# Regulator.net
KiCad netlist of a schematic drawn in Altium Designer
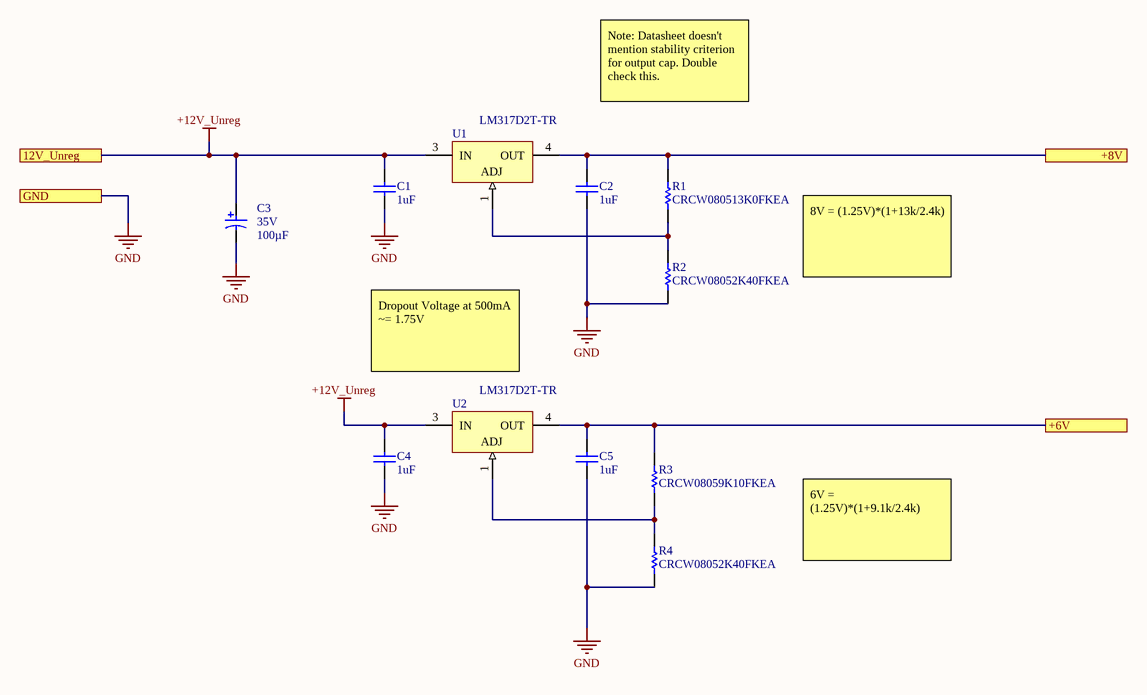
[diagram p0: Regulator.SchDoc]

(export (version "E")
  (design (tool "Eeschema 10.0.6"))
  (components
    (comp (ref "C1")
      (value "1uF")
      (footprint "CAPC2013X100X50NL20T25")
      (fields (field (name "PART NUMBER") "C0805X105K3RACTU") (field (name "MANUFACTURER") "Kemet"))
      (libsource (lib "Altium Content Vault") (part "CAP"))
    )
    (comp (ref "C2")
      (value "1uF")
      (footprint "CAPC2013X100X50NL20T25")
      (fields (field (name "PART NUMBER") "C0805X105K3RACTU") (field (name "MANUFACTURER") "Kemet"))
      (libsource (lib "Altium Content Vault") (part "CAP"))
    )
    (comp (ref "C3")
      (value "EEEFC1V101P")
      (footprint "PNSC-FC-V-G_V")
      (fields
        (field (name "CAPACITANCE") "100µF")
        (field (name "MANUFACTURER") "Panasonic")
        (field (name "VOLTAGE RATING") "35V")
      )
      (libsource (lib "Altium Content Vault") (part "CAP-P-2"))
    )
    (comp (ref "C4")
      (value "1uF")
      (footprint "CAPC2013X100X50NL20T25")
      (fields (field (name "PART NUMBER") "C0805X105K3RACTU") (field (name "MANUFACTURER") "Kemet"))
      (libsource (lib "Altium Content Vault") (part "CAP"))
    )
    (comp (ref "C5")
      (value "1uF")
      (footprint "CAPC2013X100X50NL20T25")
      (fields (field (name "PART NUMBER") "C0805X105K3RACTU") (field (name "MANUFACTURER") "Kemet"))
      (libsource (lib "Altium Content Vault") (part "CAP"))
    )
    (comp (ref "R1")
      (value "CRCW080513K0FKEA")
      (footprint "RESC2013X50X30LL20T20")
      (fields (field (name "MANUFACTURER") "Vishay Dale"))
      (libsource (lib "Altium Content Vault") (part "RES"))
    )
    (comp (ref "R2")
      (value "CRCW08052K40FKEA")
      (footprint "RESC2013X50X30NL20T20")
      (fields (field (name "MANUFACTURER") "Vishay Dale"))
      (libsource (lib "Altium Content Vault") (part "RES"))
    )
    (comp (ref "R3")
      (value "CRCW08059K10FKEA")
      (footprint "RESC2013X50X30ML20T20")
      (fields (field (name "MANUFACTURER") "Vishay Dale"))
      (libsource (lib "Altium Content Vault") (part "RES"))
    )
    (comp (ref "R4")
      (value "CRCW08052K40FKEA")
      (footprint "RESC2013X50X30NL20T20")
      (fields (field (name "MANUFACTURER") "Vishay Dale"))
      (libsource (lib "Altium Content Vault") (part "RES"))
    )
    (comp (ref "U1")
      (value "LM317D2T-TR")
      (footprint "TO-263_N")
      (description "1.5A, 1.2V to 37V Adjustable Voltage Regulator, 3-Pin D2PAK, Tape and Reel")
      (libsource (lib "Altium Content Vault") (part "PM-REG-217-SOT3"))
    )
    (comp (ref "U2")
      (value "LM317D2T-TR")
      (footprint "TO-263_N")
      (description "1.5A, 1.2V to 37V Adjustable Voltage Regulator, 3-Pin D2PAK, Tape and Reel")
      (libsource (lib "Altium Content Vault") (part "PM-REG-217-SOT3"))
    )
  )
  (nets
    (net (code "1") (name "+12V_Unreg") (class "Default")
      (node (ref "C1") (pin "2") (pinfunction "2_2") (pintype "passive"))
      (node (ref "C3") (pin "1") (pinfunction "1_1") (pintype "passive"))
      (node (ref "C4") (pin "2") (pinfunction "2_2") (pintype "passive"))
      (node (ref "U1") (pin "3") (pinfunction "IN_3") (pintype "power_in"))
      (node (ref "U2") (pin "3") (pinfunction "IN_3") (pintype "power_in"))
    )
    (net (code "2") (name "/+6V") (class "Default")
      (node (ref "C5") (pin "2") (pinfunction "2_2") (pintype "passive"))
      (node (ref "R3") (pin "2") (pinfunction "2_2") (pintype "passive"))
      (node (ref "U2") (pin "4") (pinfunction "OUT_4") (pintype "power_in"))
    )
    (net (code "3") (name "/+8V") (class "Default")
      (node (ref "C2") (pin "2") (pinfunction "2_2") (pintype "passive"))
      (node (ref "R1") (pin "2") (pinfunction "2_2") (pintype "passive"))
      (node (ref "U1") (pin "4") (pinfunction "OUT_4") (pintype "power_in"))
    )
    (net (code "4") (name "GND") (class "Default")
      (node (ref "C1") (pin "1") (pinfunction "1_1") (pintype "passive"))
      (node (ref "C2") (pin "1") (pinfunction "1_1") (pintype "passive"))
      (node (ref "C3") (pin "2") (pinfunction "2_2") (pintype "passive"))
      (node (ref "C4") (pin "1") (pinfunction "1_1") (pintype "passive"))
      (node (ref "C5") (pin "1") (pinfunction "1_1") (pintype "passive"))
      (node (ref "R2") (pin "2") (pinfunction "2_2") (pintype "passive"))
      (node (ref "R4") (pin "2") (pinfunction "2_2") (pintype "passive"))
    )
    (net (code "5") (name "Net-(U1-ADJ)") (class "Default")
      (node (ref "R1") (pin "1") (pinfunction "1_1") (pintype "passive"))
      (node (ref "R2") (pin "1") (pinfunction "1_1") (pintype "passive"))
      (node (ref "U1") (pin "1") (pinfunction "ADJ_1") (pintype "input"))
    )
    (net (code "6") (name "Net-(U2-ADJ)") (class "Default")
      (node (ref "R3") (pin "1") (pinfunction "1_1") (pintype "passive"))
      (node (ref "R4") (pin "1") (pinfunction "1_1") (pintype "passive"))
      (node (ref "U2") (pin "1") (pinfunction "ADJ_1") (pintype "input"))
    )
  )
)
